# 01_interface.net
KiCad netlist of a schematic drawn in Altium Designer
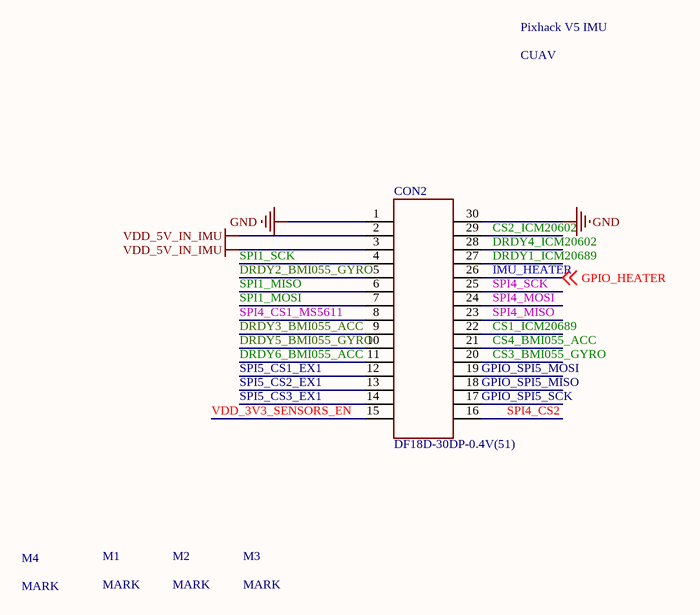
[diagram p0: 01_interface.SchDoc]

(export (version "E")
  (design (tool "Eeschema 10.0.6"))
  (components
    (comp (ref "CON2")
      (value "DF18D-30DP-0.4V(51)")
      (footprint "DF18D-30DP-0.4V(51)")
      (libsource (lib "CUAV") (part "DF18D-30DP-0.4V(51)"))
    )
    (comp (ref "M1") (value "MARK") (footprint "MARK") (libsource (lib "CUAV") (part "MARK")))
    (comp (ref "M2") (value "MARK") (footprint "MARK") (libsource (lib "CUAV") (part "MARK")))
    (comp (ref "M3") (value "MARK") (footprint "MARK") (libsource (lib "CUAV") (part "MARK")))
    (comp (ref "M4") (value "MARK") (footprint "MARK") (libsource (lib "CUAV") (part "MARK")))
    (comp (ref "Pixhack V5 IMU") (value "CUAV") (footprint "CUAV") (libsource (lib "CUAV") (part "CUAV")))
  )
  (nets
    (net (code "1") (name "/CS1_ICM20689") (class "Default")
      (node (ref "CON2") (pin "22") (pintype "passive"))
    )
    (net (code "2") (name "/CS2_ICM20602") (class "Default")
      (node (ref "CON2") (pin "29") (pintype "passive"))
    )
    (net (code "3") (name "/CS3_BMI055_GYRO") (class "Default")
      (node (ref "CON2") (pin "20") (pintype "passive"))
    )
    (net (code "4") (name "/CS4_BMI055_ACC") (class "Default")
      (node (ref "CON2") (pin "21") (pintype "passive"))
    )
    (net (code "5") (name "/DRDY1_ICM20689") (class "Default")
      (node (ref "CON2") (pin "27") (pintype "passive"))
    )
    (net (code "6") (name "/DRDY2_BMI055_GYRO") (class "Default")
      (node (ref "CON2") (pin "5") (pintype "passive"))
    )
    (net (code "7") (name "/DRDY3_BMI055_ACC") (class "Default")
      (node (ref "CON2") (pin "9") (pintype "passive"))
    )
    (net (code "8") (name "/DRDY4_ICM20602") (class "Default")
      (node (ref "CON2") (pin "28") (pintype "passive"))
    )
    (net (code "9") (name "/DRDY5_BMI055_GYRO") (class "Default")
      (node (ref "CON2") (pin "10") (pintype "passive"))
    )
    (net (code "10") (name "/DRDY6_BMI055_ACC") (class "Default")
      (node (ref "CON2") (pin "11") (pintype "passive"))
    )
    (net (code "11") (name "/GPIO_SPI5_MISO") (class "Default")
      (node (ref "CON2") (pin "18") (pintype "passive"))
    )
    (net (code "12") (name "/GPIO_SPI5_MOSI") (class "Default")
      (node (ref "CON2") (pin "19") (pintype "passive"))
    )
    (net (code "13") (name "/GPIO_SPI5_SCK") (class "Default")
      (node (ref "CON2") (pin "17") (pintype "passive"))
    )
    (net (code "14") (name "/SPI1_MISO") (class "Default") (node (ref "CON2") (pin "6") (pintype "passive")))
    (net (code "15") (name "/SPI1_MOSI") (class "Default") (node (ref "CON2") (pin "7") (pintype "passive")))
    (net (code "16") (name "/SPI1_SCK") (class "Default") (node (ref "CON2") (pin "4") (pintype "passive")))
    (net (code "17") (name "/SPI4_CS1_MS5611") (class "Default")
      (node (ref "CON2") (pin "8") (pintype "passive"))
    )
    (net (code "18") (name "/SPI4_CS2") (class "Default") (node (ref "CON2") (pin "16") (pintype "passive")))
    (net (code "19") (name "/SPI4_MISO") (class "Default") (node (ref "CON2") (pin "23") (pintype "passive")))
    (net (code "20") (name "/SPI4_MOSI") (class "Default") (node (ref "CON2") (pin "24") (pintype "passive")))
    (net (code "21") (name "/SPI4_SCK") (class "Default") (node (ref "CON2") (pin "25") (pintype "passive")))
    (net (code "22") (name "/SPI5_CS1_EX1") (class "Default")
      (node (ref "CON2") (pin "12") (pintype "passive"))
    )
    (net (code "23") (name "/SPI5_CS2_EX1") (class "Default")
      (node (ref "CON2") (pin "13") (pintype "passive"))
    )
    (net (code "24") (name "/SPI5_CS3_EX1") (class "Default")
      (node (ref "CON2") (pin "14") (pintype "passive"))
    )
    (net (code "25") (name "/VDD_3V3_SENSORS_EN") (class "Default")
      (node (ref "CON2") (pin "15") (pintype "passive"))
    )
    (net (code "26") (name "GND") (class "Default")
      (node (ref "CON2") (pin "1") (pintype "passive"))
      (node (ref "CON2") (pin "30") (pintype "passive"))
    )
    (net (code "27") (name "GPIO_HEATER") (class "Default")
      (node (ref "CON2") (pin "26") (pintype "passive"))
    )
    (net (code "28") (name "VDD_5V_IN_IMU") (class "Default")
      (node (ref "CON2") (pin "2") (pintype "passive"))
      (node (ref "CON2") (pin "3") (pintype "passive"))
    )
  )
)
